# STM32F103C8T6.net
KiCad netlist of a schematic drawn in Altium Designer
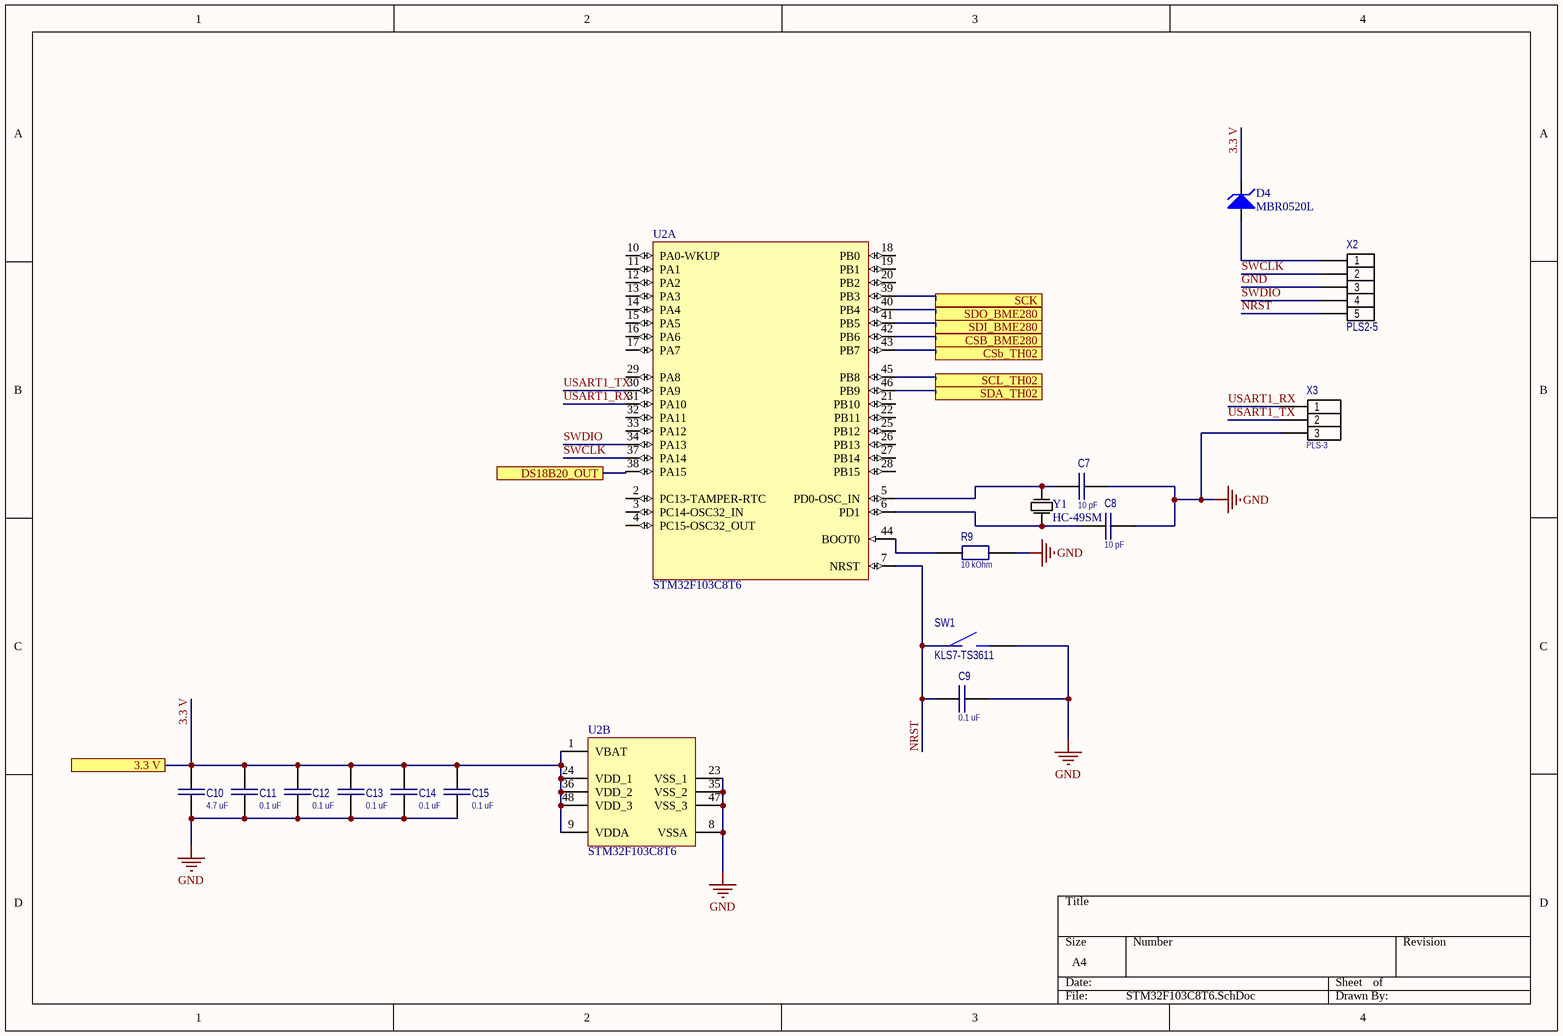
[diagram p0: STM32F103C8T6.SchDoc]

(export (version "E")
  (design (tool "Eeschema 10.0.6"))
  (components
    (comp (ref "C7")
      (value "10 pF")
      (footprint "C_0805")
      (description "Capacitor")
      (libsource (lib "capacitors") (part "C0805"))
    )
    (comp (ref "C8")
      (value "10 pF")
      (footprint "C_0805")
      (description "Capacitor")
      (libsource (lib "capacitors") (part "C0805"))
    )
    (comp (ref "C9")
      (value "0.1 uF")
      (footprint "C_0805")
      (description "Capacitor")
      (libsource (lib "capacitors") (part "C0805"))
    )
    (comp (ref "C10")
      (value "4.7 uF")
      (footprint "C_0805")
      (description "Capacitor")
      (libsource (lib "capacitors") (part "C0805"))
    )
    (comp (ref "C11")
      (value "0.1 uF")
      (footprint "C_0805")
      (description "Capacitor")
      (libsource (lib "capacitors") (part "C0805"))
    )
    (comp (ref "C12")
      (value "0.1 uF")
      (footprint "C_0805")
      (description "Capacitor")
      (libsource (lib "capacitors") (part "C0805"))
    )
    (comp (ref "C13")
      (value "0.1 uF")
      (footprint "C_0805")
      (description "Capacitor")
      (libsource (lib "capacitors") (part "C0805"))
    )
    (comp (ref "C14")
      (value "0.1 uF")
      (footprint "C_0805")
      (description "Capacitor")
      (libsource (lib "capacitors") (part "C0805"))
    )
    (comp (ref "C15")
      (value "0.1 uF")
      (footprint "C_0805")
      (description "Capacitor")
      (libsource (lib "capacitors") (part "C0805"))
    )
    (comp (ref "D4")
      (value "MBR0520L")
      (footprint "SOD-123")
      (description "Surface Mount Zener Diode")
      (fields (field (name "PUBLISHER") "Altium Limited"))
      (libsource (lib "diode") (part "DZ_SOD123"))
    )
    (comp (ref "R9")
      (value "10 kOhm")
      (footprint "R_0805")
      (description "Resistor")
      (libsource (lib "resistors") (part "R0805"))
    )
    (comp (ref "SW1")
      (value "KLS7-TS3611")
      (footprint "KLS7-TS3611")
      (libsource (lib "other") (part "button"))
    )
    (comp (ref "U2")
      (value "STM32F103C8T6")
      (footprint "LQFP48_N")
      (libsource (lib "STM32 F1") (part "STM32F103C8T6"))
    )
    (comp (ref "X2")
      (value "PLS2-5")
      (footprint "PLS-5-2")
      (description "Header, 5-Pin")
      (fields (field (name "PUBLISHER") "Altium Limited"))
      (libsource (lib "connectors_socets") (part "PLS2-5"))
    )
    (comp (ref "X3")
      (value "PLS-3")
      (footprint "PLS-3-3D")
      (description "Header, 3-Pin")
      (fields (field (name "PUBLISHER") "Altium Limited"))
      (libsource (lib "connectors_socets") (part "PLS-3"))
    )
    (comp (ref "Y1")
      (value "HC-49SM")
      (footprint "HC-49SM")
      (libsource (lib "crystals_oscillators") (part "HC-49SM"))
    )
  )
  (nets
    (net (code "1") (name "/3.3 V") (class "Default")
      (node (ref "C10") (pin "2") (pinfunction "2_2") (pintype "passive"))
      (node (ref "C11") (pin "2") (pinfunction "2_2") (pintype "passive"))
      (node (ref "C12") (pin "2") (pinfunction "2_2") (pintype "passive"))
      (node (ref "C13") (pin "2") (pinfunction "2_2") (pintype "passive"))
      (node (ref "C14") (pin "2") (pinfunction "2_2") (pintype "passive"))
      (node (ref "C15") (pin "2") (pinfunction "2_2") (pintype "passive"))
      (node (ref "D4") (pin "2") (pinfunction "K_2") (pintype "passive"))
      (node (ref "U2") (pin "1") (pinfunction "VBAT_1") (pintype "power_in"))
      (node (ref "U2") (pin "24") (pinfunction "VDD_1_24") (pintype "power_in"))
      (node (ref "U2") (pin "36") (pinfunction "VDD_2_36") (pintype "power_in"))
      (node (ref "U2") (pin "48") (pinfunction "VDD_3_48") (pintype "power_in"))
      (node (ref "U2") (pin "9") (pinfunction "VDDA_9") (pintype "power_in"))
    )
    (net (code "2") (name "/CSB_BME280") (class "Default")
      (node (ref "U2") (pin "42") (pinfunction "PB6_42") (pintype "bidirectional"))
    )
    (net (code "3") (name "/CSb_TH02") (class "Default")
      (node (ref "U2") (pin "43") (pinfunction "PB7_43") (pintype "bidirectional"))
    )
    (net (code "4") (name "/DS18B20_OUT") (class "Default")
      (node (ref "U2") (pin "38") (pinfunction "PA15_38") (pintype "bidirectional"))
    )
    (net (code "5") (name "/NRST") (class "Default")
      (node (ref "C9") (pin "2") (pinfunction "2_2") (pintype "passive"))
      (node (ref "SW1") (pin "1") (pinfunction "1_1") (pintype "passive"))
      (node (ref "U2") (pin "7") (pinfunction "NRST_7") (pintype "bidirectional"))
      (node (ref "X2") (pin "5") (pinfunction "5_5") (pintype "passive"))
    )
    (net (code "6") (name "/SCK") (class "Default")
      (node (ref "U2") (pin "39") (pinfunction "PB3_39") (pintype "bidirectional"))
    )
    (net (code "7") (name "/SCL_TH02") (class "Default")
      (node (ref "U2") (pin "45") (pinfunction "PB8_45") (pintype "bidirectional"))
    )
    (net (code "8") (name "/SDA_TH02") (class "Default")
      (node (ref "U2") (pin "46") (pinfunction "PB9_46") (pintype "bidirectional"))
    )
    (net (code "9") (name "/SDI_BME280") (class "Default")
      (node (ref "U2") (pin "41") (pinfunction "PB5_41") (pintype "bidirectional"))
    )
    (net (code "10") (name "/SDO_BME280") (class "Default")
      (node (ref "U2") (pin "40") (pinfunction "PB4_40") (pintype "bidirectional"))
    )
    (net (code "11") (name "/SWCLK") (class "Default")
      (node (ref "U2") (pin "37") (pinfunction "PA14_37") (pintype "bidirectional"))
      (node (ref "X2") (pin "2") (pinfunction "2_2") (pintype "passive"))
    )
    (net (code "12") (name "/SWDIO") (class "Default")
      (node (ref "U2") (pin "34") (pinfunction "PA13_34") (pintype "bidirectional"))
      (node (ref "X2") (pin "4") (pinfunction "4_4") (pintype "passive"))
    )
    (net (code "13") (name "/USART1_RX") (class "Default")
      (node (ref "U2") (pin "31") (pinfunction "PA10_31") (pintype "bidirectional"))
      (node (ref "X3") (pin "1") (pinfunction "1_1") (pintype "passive"))
    )
    (net (code "14") (name "/USART1_TX") (class "Default")
      (node (ref "U2") (pin "30") (pinfunction "PA9_30") (pintype "bidirectional"))
      (node (ref "X3") (pin "2") (pinfunction "2_2") (pintype "passive"))
    )
    (net (code "15") (name "GND") (class "Default")
      (node (ref "C10") (pin "1") (pinfunction "1_1") (pintype "passive"))
      (node (ref "C11") (pin "1") (pinfunction "1_1") (pintype "passive"))
      (node (ref "C12") (pin "1") (pinfunction "1_1") (pintype "passive"))
      (node (ref "C13") (pin "1") (pinfunction "1_1") (pintype "passive"))
      (node (ref "C14") (pin "1") (pinfunction "1_1") (pintype "passive"))
      (node (ref "C15") (pin "1") (pinfunction "1_1") (pintype "passive"))
      (node (ref "C7") (pin "1") (pinfunction "1_1") (pintype "passive"))
      (node (ref "C8") (pin "1") (pinfunction "1_1") (pintype "passive"))
      (node (ref "C9") (pin "1") (pinfunction "1_1") (pintype "passive"))
      (node (ref "R9") (pin "1") (pinfunction "1_1") (pintype "passive"))
      (node (ref "SW1") (pin "2") (pinfunction "2_2") (pintype "passive"))
      (node (ref "U2") (pin "23") (pinfunction "VSS_1_23") (pintype "power_in"))
      (node (ref "U2") (pin "35") (pinfunction "VSS_2_35") (pintype "power_in"))
      (node (ref "U2") (pin "47") (pinfunction "VSS_3_47") (pintype "power_in"))
      (node (ref "U2") (pin "8") (pinfunction "VSSA_8") (pintype "power_in"))
      (node (ref "X2") (pin "3") (pinfunction "3_3") (pintype "passive"))
      (node (ref "X3") (pin "3") (pinfunction "3_3") (pintype "passive"))
    )
    (net (code "16") (name "Net-(D4-A)") (class "Default")
      (node (ref "D4") (pin "1") (pinfunction "A_1") (pintype "passive"))
      (node (ref "X2") (pin "1") (pinfunction "1_1") (pintype "passive"))
    )
    (net (code "17") (name "Net-(U2A-BOOT0)") (class "Default")
      (node (ref "R9") (pin "2") (pinfunction "2_2") (pintype "passive"))
      (node (ref "U2") (pin "44") (pinfunction "BOOT0_44") (pintype "input"))
    )
    (net (code "18") (name "Net-(U2A-PD0-OSC_IN)") (class "Default")
      (node (ref "C7") (pin "2") (pinfunction "2_2") (pintype "passive"))
      (node (ref "U2") (pin "5") (pinfunction "PD0-OSC_IN_5") (pintype "bidirectional"))
      (node (ref "Y1") (pin "2") (pinfunction "OSC2_2") (pintype "passive"))
    )
    (net (code "19") (name "Net-(U2A-PD1)") (class "Default")
      (node (ref "C8") (pin "2") (pinfunction "2_2") (pintype "passive"))
      (node (ref "U2") (pin "6") (pinfunction "PD1_6") (pintype "bidirectional"))
      (node (ref "Y1") (pin "1") (pinfunction "OSC1_1") (pintype "passive"))
    )
    (net (code "20") (name "unconnected-(U2A-PA0-WKUP-Pad10)") (class "Default")
      (node (ref "U2") (pin "10") (pinfunction "PA0-WKUP_10") (pintype "bidirectional"))
    )
    (net (code "21") (name "unconnected-(U2A-PA1-Pad11)") (class "Default")
      (node (ref "U2") (pin "11") (pinfunction "PA1_11") (pintype "bidirectional"))
    )
    (net (code "22") (name "unconnected-(U2A-PA2-Pad12)") (class "Default")
      (node (ref "U2") (pin "12") (pinfunction "PA2_12") (pintype "bidirectional"))
    )
    (net (code "23") (name "unconnected-(U2A-PA3-Pad13)") (class "Default")
      (node (ref "U2") (pin "13") (pinfunction "PA3_13") (pintype "bidirectional"))
    )
    (net (code "24") (name "unconnected-(U2A-PA4-Pad14)") (class "Default")
      (node (ref "U2") (pin "14") (pinfunction "PA4_14") (pintype "bidirectional"))
    )
    (net (code "25") (name "unconnected-(U2A-PA5-Pad15)") (class "Default")
      (node (ref "U2") (pin "15") (pinfunction "PA5_15") (pintype "bidirectional"))
    )
    (net (code "26") (name "unconnected-(U2A-PA6-Pad16)") (class "Default")
      (node (ref "U2") (pin "16") (pinfunction "PA6_16") (pintype "bidirectional"))
    )
    (net (code "27") (name "unconnected-(U2A-PA7-Pad17)") (class "Default")
      (node (ref "U2") (pin "17") (pinfunction "PA7_17") (pintype "bidirectional"))
    )
    (net (code "28") (name "unconnected-(U2A-PA8-Pad29)") (class "Default")
      (node (ref "U2") (pin "29") (pinfunction "PA8_29") (pintype "bidirectional"))
    )
    (net (code "29") (name "unconnected-(U2A-PA11-Pad32)") (class "Default")
      (node (ref "U2") (pin "32") (pinfunction "PA11_32") (pintype "bidirectional"))
    )
    (net (code "30") (name "unconnected-(U2A-PA12-Pad33)") (class "Default")
      (node (ref "U2") (pin "33") (pinfunction "PA12_33") (pintype "bidirectional"))
    )
    (net (code "31") (name "unconnected-(U2A-PB0-Pad18)") (class "Default")
      (node (ref "U2") (pin "18") (pinfunction "PB0_18") (pintype "bidirectional"))
    )
    (net (code "32") (name "unconnected-(U2A-PB1-Pad19)") (class "Default")
      (node (ref "U2") (pin "19") (pinfunction "PB1_19") (pintype "bidirectional"))
    )
    (net (code "33") (name "unconnected-(U2A-PB2-Pad20)") (class "Default")
      (node (ref "U2") (pin "20") (pinfunction "PB2_20") (pintype "bidirectional"))
    )
    (net (code "34") (name "unconnected-(U2A-PB10-Pad21)") (class "Default")
      (node (ref "U2") (pin "21") (pinfunction "PB10_21") (pintype "bidirectional"))
    )
    (net (code "35") (name "unconnected-(U2A-PB11-Pad22)") (class "Default")
      (node (ref "U2") (pin "22") (pinfunction "PB11_22") (pintype "bidirectional"))
    )
    (net (code "36") (name "unconnected-(U2A-PB12-Pad25)") (class "Default")
      (node (ref "U2") (pin "25") (pinfunction "PB12_25") (pintype "bidirectional"))
    )
    (net (code "37") (name "unconnected-(U2A-PB13-Pad26)") (class "Default")
      (node (ref "U2") (pin "26") (pinfunction "PB13_26") (pintype "bidirectional"))
    )
    (net (code "38") (name "unconnected-(U2A-PB14-Pad27)") (class "Default")
      (node (ref "U2") (pin "27") (pinfunction "PB14_27") (pintype "bidirectional"))
    )
    (net (code "39") (name "unconnected-(U2A-PB15-Pad28)") (class "Default")
      (node (ref "U2") (pin "28") (pinfunction "PB15_28") (pintype "bidirectional"))
    )
    (net (code "40") (name "unconnected-(U2A-PC13-TAMPER-RTC-Pad2)") (class "Default")
      (node (ref "U2") (pin "2") (pinfunction "PC13-TAMPER-RTC_2") (pintype "bidirectional"))
    )
    (net (code "41") (name "unconnected-(U2A-PC14-OSC32_IN-Pad3)") (class "Default")
      (node (ref "U2") (pin "3") (pinfunction "PC14-OSC32_IN_3") (pintype "bidirectional"))
    )
    (net (code "42") (name "unconnected-(U2A-PC15-OSC32_OUT-Pad4)") (class "Default")
      (node (ref "U2") (pin "4") (pinfunction "PC15-OSC32_OUT_4") (pintype "bidirectional"))
    )
  )
)
